# had_ret.net
KiCad netlist of a schematic drawn in EAGLE
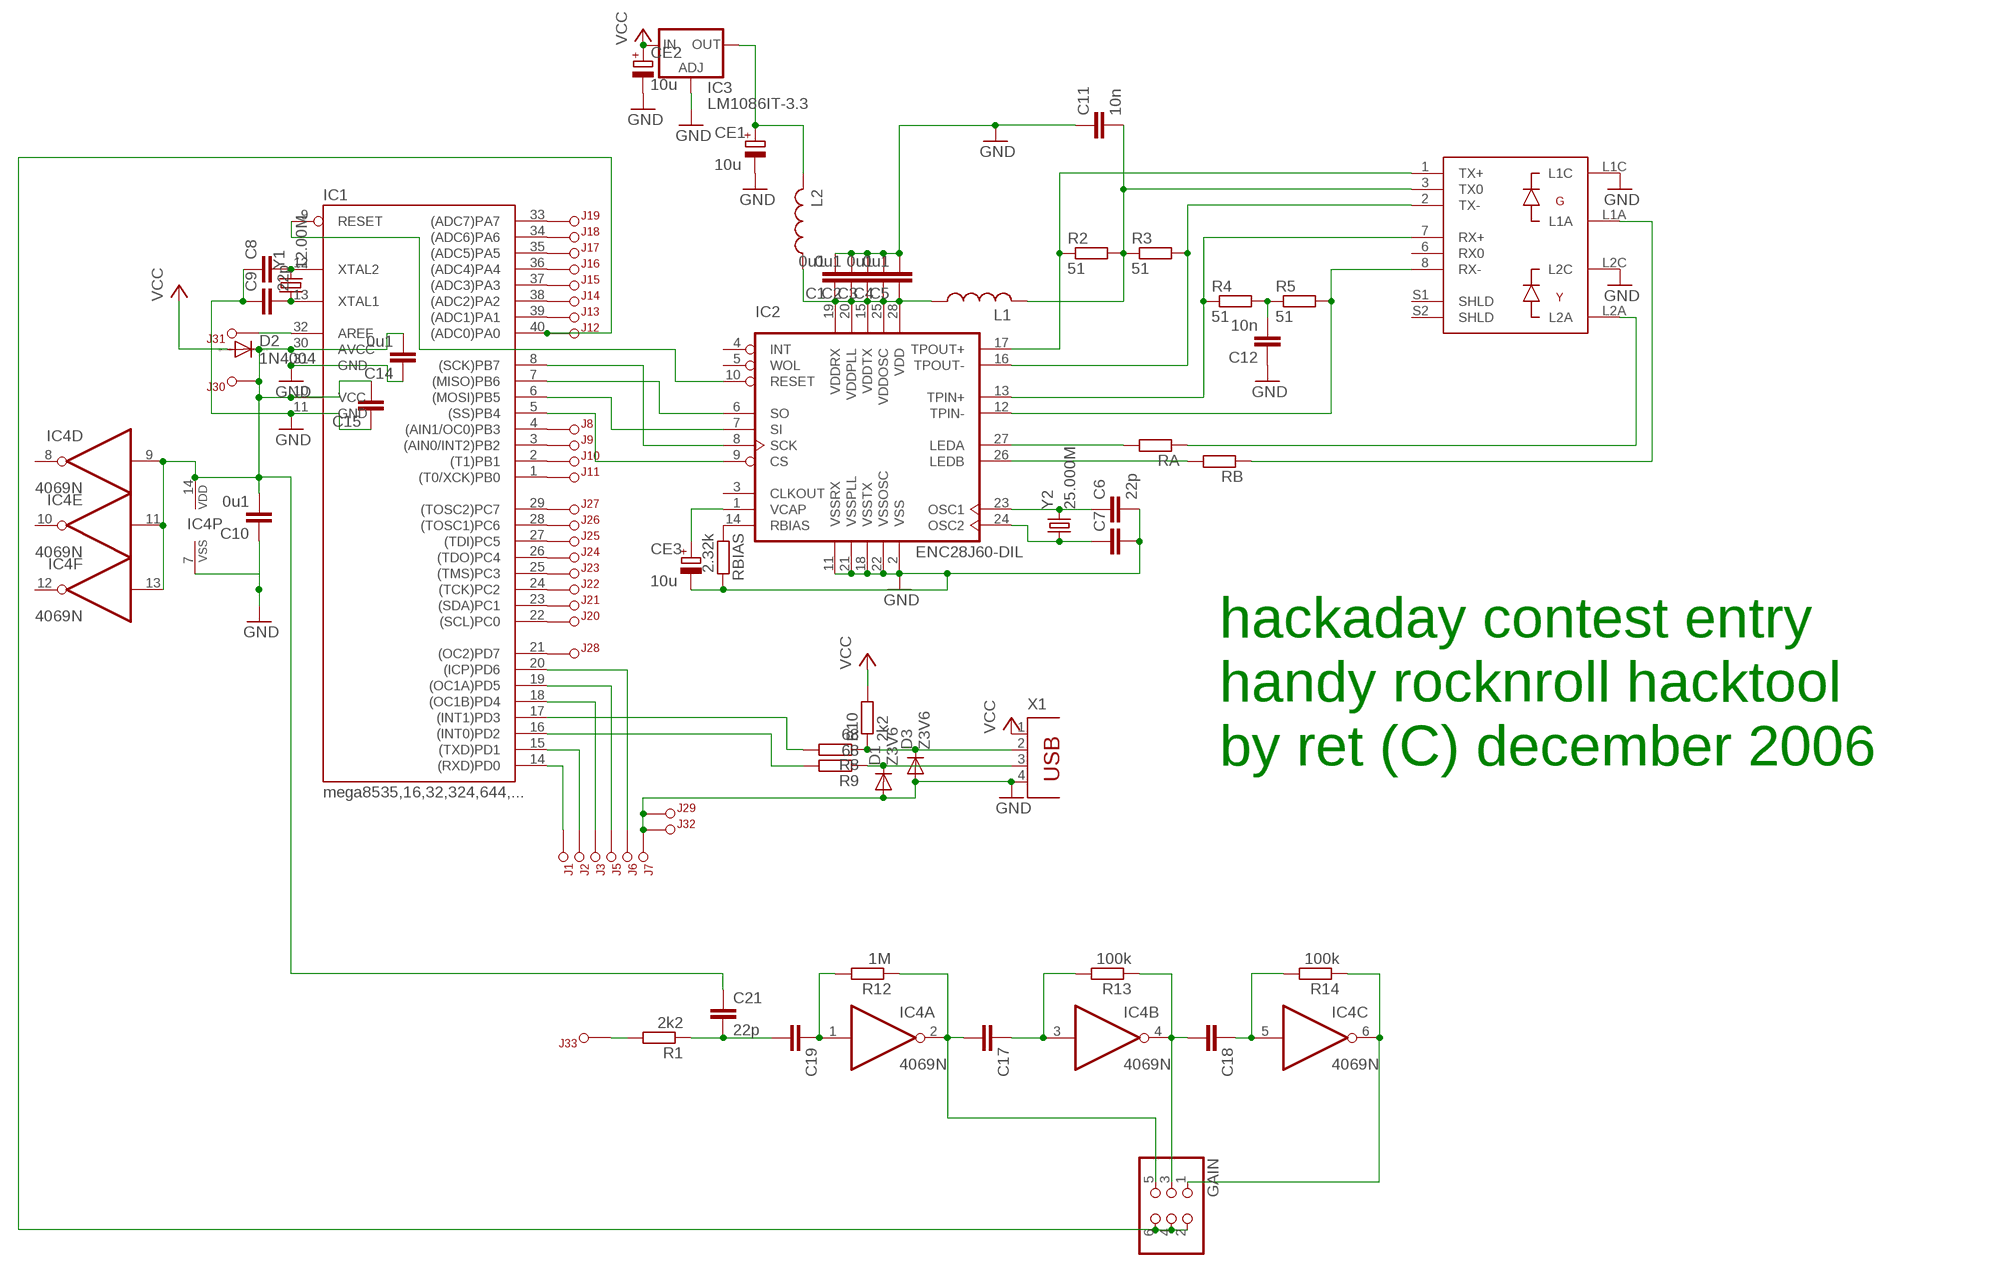
[diagram p0: schematic, sheet 1]

(export (version "E")
  (design (tool "Eeschema 10.0.6"))
  (components
    (comp (ref "C1")
      (value "0u1")
      (footprint "eagle-import:0805")
      (libsource (lib "eagle-import") (part "C0805"))
    )
    (comp (ref "C2")
      (value "0u1")
      (footprint "eagle-import:0805")
      (libsource (lib "eagle-import") (part "C0805"))
    )
    (comp (ref "C3")
      (value "C0805")
      (footprint "eagle-import:0805")
      (libsource (lib "eagle-import") (part "C0805"))
    )
    (comp (ref "C4")
      (value "0u1")
      (footprint "eagle-import:0805")
      (libsource (lib "eagle-import") (part "C0805"))
    )
    (comp (ref "C5")
      (value "0u1")
      (footprint "eagle-import:0805")
      (libsource (lib "eagle-import") (part "C0805"))
    )
    (comp (ref "C6")
      (value "22p")
      (footprint "eagle-import:0805")
      (libsource (lib "eagle-import") (part "C0805"))
    )
    (comp (ref "C7")
      (value "C0805")
      (footprint "eagle-import:0805")
      (libsource (lib "eagle-import") (part "C0805"))
    )
    (comp (ref "C8")
      (value "C0805")
      (footprint "eagle-import:0805")
      (libsource (lib "eagle-import") (part "C0805"))
    )
    (comp (ref "C9")
      (value "22p")
      (footprint "eagle-import:0805")
      (libsource (lib "eagle-import") (part "C0805"))
    )
    (comp (ref "C10")
      (value "0u1")
      (footprint "eagle-import:0805")
      (libsource (lib "eagle-import") (part "C0805"))
    )
    (comp (ref "C11")
      (value "10n")
      (footprint "eagle-import:0805")
      (libsource (lib "eagle-import") (part "C0805"))
    )
    (comp (ref "C12")
      (value "10n")
      (footprint "eagle-import:0805")
      (libsource (lib "eagle-import") (part "C0805"))
    )
    (comp (ref "C14")
      (value "0u1")
      (footprint "eagle-import:0805")
      (libsource (lib "eagle-import") (part "C0805"))
    )
    (comp (ref "C15")
      (value "C0805")
      (footprint "eagle-import:0805")
      (libsource (lib "eagle-import") (part "C0805"))
    )
    (comp (ref "C17")
      (value "C0805")
      (footprint "eagle-import:0805")
      (libsource (lib "eagle-import") (part "C0805"))
    )
    (comp (ref "C18")
      (value "C0805")
      (footprint "eagle-import:0805")
      (libsource (lib "eagle-import") (part "C0805"))
    )
    (comp (ref "C19")
      (value "C0805")
      (footprint "eagle-import:0805")
      (libsource (lib "eagle-import") (part "C0805"))
    )
    (comp (ref "C21")
      (value "22p")
      (footprint "eagle-import:0805")
      (libsource (lib "eagle-import") (part "C0805"))
    )
    (comp (ref "CE1")
      (value "10u")
      (footprint "eagle-import:CT3528")
      (libsource (lib "eagle-import") (part "CPOL-EUCT3528"))
    )
    (comp (ref "CE2")
      (value "10u")
      (footprint "eagle-import:CT3528")
      (libsource (lib "eagle-import") (part "CPOL-EUCT3528"))
    )
    (comp (ref "CE3")
      (value "10u")
      (footprint "eagle-import:CT3528")
      (libsource (lib "eagle-import") (part "CPOL-EUCT3528"))
    )
    (comp (ref "D1")
      (value "Z3V6")
      (footprint "eagle-import:DIODE")
      (libsource (lib "eagle-import") (part "DIODE"))
    )
    (comp (ref "D2")
      (value "1N4004")
      (footprint "eagle-import:DO41-10")
      (libsource (lib "eagle-import") (part "1N4004"))
    )
    (comp (ref "D3")
      (value "Z3V6")
      (footprint "eagle-import:DIODE")
      (libsource (lib "eagle-import") (part "DIODE"))
    )
    (comp (ref "GAIN")
      (value "PINHD-2X3")
      (footprint "eagle-import:2X03")
      (libsource (lib "eagle-import") (part "PINHD-2X3"))
    )
    (comp (ref "IC1")
      (value "mega8535,16,32,324,644,...")
      (footprint "eagle-import:DIL40")
      (fields (field (name "MPN") "ATMEGA16-16PU"))
      (libsource (lib "eagle-import") (part "MEGA16-P"))
    )
    (comp (ref "IC2")
      (value "ENC28J60-DIL")
      (footprint "eagle-import:DIL28-3")
      (libsource (lib "eagle-import") (part "ENC28J60-DIL"))
    )
    (comp (ref "IC3")
      (value "LM1086IT-3.3")
      (footprint "eagle-import:317TS")
      (libsource (lib "eagle-import") (part "LM317TS"))
    )
    (comp (ref "IC4")
      (value "4069N")
      (footprint "eagle-import:DIL14")
      (libsource (lib "eagle-import") (part "4069N"))
    )
    (comp (ref "J1")
      (value "PINMA01")
      (footprint "eagle-import:MA01-1PIN")
      (libsource (lib "eagle-import") (part "PINMA01"))
    )
    (comp (ref "J2")
      (value "PINMA01")
      (footprint "eagle-import:MA01-1PIN")
      (libsource (lib "eagle-import") (part "PINMA01"))
    )
    (comp (ref "J3")
      (value "PINMA01")
      (footprint "eagle-import:MA01-1PIN")
      (libsource (lib "eagle-import") (part "PINMA01"))
    )
    (comp (ref "J4")
      (value "8P8C-TRAF")
      (footprint "eagle-import:8P8C-TRAF")
      (libsource (lib "eagle-import") (part "8P8C-TRAF"))
    )
    (comp (ref "J5")
      (value "PINMA01")
      (footprint "eagle-import:MA01-1PIN")
      (libsource (lib "eagle-import") (part "PINMA01"))
    )
    (comp (ref "J6")
      (value "PINMA01")
      (footprint "eagle-import:MA01-1PIN")
      (libsource (lib "eagle-import") (part "PINMA01"))
    )
    (comp (ref "J7")
      (value "PINMA01")
      (footprint "eagle-import:MA01-1PIN")
      (libsource (lib "eagle-import") (part "PINMA01"))
    )
    (comp (ref "J8")
      (value "PINMA01")
      (footprint "eagle-import:MA01-1PIN")
      (libsource (lib "eagle-import") (part "PINMA01"))
    )
    (comp (ref "J9")
      (value "PINMA01")
      (footprint "eagle-import:MA01-1PIN")
      (libsource (lib "eagle-import") (part "PINMA01"))
    )
    (comp (ref "J10")
      (value "PINMA01")
      (footprint "eagle-import:MA01-1PIN")
      (libsource (lib "eagle-import") (part "PINMA01"))
    )
    (comp (ref "J11")
      (value "PINMA01")
      (footprint "eagle-import:MA01-1PIN")
      (libsource (lib "eagle-import") (part "PINMA01"))
    )
    (comp (ref "J12")
      (value "PINMA01")
      (footprint "eagle-import:MA01-1PIN")
      (libsource (lib "eagle-import") (part "PINMA01"))
    )
    (comp (ref "J13")
      (value "PINMA01")
      (footprint "eagle-import:MA01-1PIN")
      (libsource (lib "eagle-import") (part "PINMA01"))
    )
    (comp (ref "J14")
      (value "PINMA01")
      (footprint "eagle-import:MA01-1PIN")
      (libsource (lib "eagle-import") (part "PINMA01"))
    )
    (comp (ref "J15")
      (value "PINMA01")
      (footprint "eagle-import:MA01-1PIN")
      (libsource (lib "eagle-import") (part "PINMA01"))
    )
    (comp (ref "J16")
      (value "PINMA01")
      (footprint "eagle-import:MA01-1PIN")
      (libsource (lib "eagle-import") (part "PINMA01"))
    )
    (comp (ref "J17")
      (value "PINMA01")
      (footprint "eagle-import:MA01-1PIN")
      (libsource (lib "eagle-import") (part "PINMA01"))
    )
    (comp (ref "J18")
      (value "PINMA01")
      (footprint "eagle-import:MA01-1PIN")
      (libsource (lib "eagle-import") (part "PINMA01"))
    )
    (comp (ref "J19")
      (value "PINMA01")
      (footprint "eagle-import:MA01-1PIN")
      (libsource (lib "eagle-import") (part "PINMA01"))
    )
    (comp (ref "J20")
      (value "PINMA01")
      (footprint "eagle-import:MA01-1PIN")
      (libsource (lib "eagle-import") (part "PINMA01"))
    )
    (comp (ref "J21")
      (value "PINMA01")
      (footprint "eagle-import:MA01-1PIN")
      (libsource (lib "eagle-import") (part "PINMA01"))
    )
    (comp (ref "J22")
      (value "PINMA01")
      (footprint "eagle-import:MA01-1PIN")
      (libsource (lib "eagle-import") (part "PINMA01"))
    )
    (comp (ref "J23")
      (value "PINMA01")
      (footprint "eagle-import:MA01-1PIN")
      (libsource (lib "eagle-import") (part "PINMA01"))
    )
    (comp (ref "J24")
      (value "PINMA01")
      (footprint "eagle-import:MA01-1PIN")
      (libsource (lib "eagle-import") (part "PINMA01"))
    )
    (comp (ref "J25")
      (value "PINMA01")
      (footprint "eagle-import:MA01-1PIN")
      (libsource (lib "eagle-import") (part "PINMA01"))
    )
    (comp (ref "J26")
      (value "PINMA01")
      (footprint "eagle-import:MA01-1PIN")
      (libsource (lib "eagle-import") (part "PINMA01"))
    )
    (comp (ref "J27")
      (value "PINMA01")
      (footprint "eagle-import:MA01-1PIN")
      (libsource (lib "eagle-import") (part "PINMA01"))
    )
    (comp (ref "J28")
      (value "PINMA01")
      (footprint "eagle-import:MA01-1PIN")
      (libsource (lib "eagle-import") (part "PINMA01"))
    )
    (comp (ref "J29")
      (value "PINMA01")
      (footprint "eagle-import:MA01-1PIN")
      (libsource (lib "eagle-import") (part "PINMA01"))
    )
    (comp (ref "J30")
      (value "PINMA01")
      (footprint "eagle-import:MA01-1PIN")
      (libsource (lib "eagle-import") (part "PINMA01"))
    )
    (comp (ref "J31")
      (value "PINMA01")
      (footprint "eagle-import:MA01-1PIN")
      (libsource (lib "eagle-import") (part "PINMA01"))
    )
    (comp (ref "J32")
      (value "PINMA01")
      (footprint "eagle-import:MA01-1PIN")
      (libsource (lib "eagle-import") (part "PINMA01"))
    )
    (comp (ref "J33")
      (value "PINMA01")
      (footprint "eagle-import:MA01-1PIN")
      (libsource (lib "eagle-import") (part "PINMA01"))
    )
    (comp (ref "L1")
      (value "L0805")
      (footprint "eagle-import:0805")
      (libsource (lib "eagle-import") (part "L0805"))
    )
    (comp (ref "L2")
      (value "L0805")
      (footprint "eagle-import:0805")
      (libsource (lib "eagle-import") (part "L0805"))
    )
    (comp (ref "R1")
      (value "2k2")
      (footprint "eagle-import:0805")
      (libsource (lib "eagle-import") (part "R0805"))
    )
    (comp (ref "R2")
      (value "51")
      (footprint "eagle-import:0805")
      (libsource (lib "eagle-import") (part "R0805"))
    )
    (comp (ref "R3")
      (value "51")
      (footprint "eagle-import:0805")
      (libsource (lib "eagle-import") (part "R0805"))
    )
    (comp (ref "R4")
      (value "51")
      (footprint "eagle-import:0805")
      (libsource (lib "eagle-import") (part "R0805"))
    )
    (comp (ref "R5")
      (value "51")
      (footprint "eagle-import:0805")
      (libsource (lib "eagle-import") (part "R0805"))
    )
    (comp (ref "R8")
      (value "68")
      (footprint "eagle-import:0805")
      (libsource (lib "eagle-import") (part "R0805"))
    )
    (comp (ref "R9")
      (value "68")
      (footprint "eagle-import:0805")
      (libsource (lib "eagle-import") (part "R0805"))
    )
    (comp (ref "R10")
      (value "2k2")
      (footprint "eagle-import:0805")
      (libsource (lib "eagle-import") (part "R0805"))
    )
    (comp (ref "R12")
      (value "1M")
      (footprint "eagle-import:0805")
      (libsource (lib "eagle-import") (part "R0805"))
    )
    (comp (ref "R13")
      (value "100k")
      (footprint "eagle-import:0805")
      (libsource (lib "eagle-import") (part "R0805"))
    )
    (comp (ref "R14")
      (value "100k")
      (footprint "eagle-import:0805")
      (libsource (lib "eagle-import") (part "R0805"))
    )
    (comp (ref "RA")
      (value "R-EU_0204/5")
      (footprint "eagle-import:0204_5")
      (libsource (lib "eagle-import") (part "R-EU_0204/5"))
    )
    (comp (ref "RB")
      (value "R-EU_0204/5")
      (footprint "eagle-import:0204_5")
      (libsource (lib "eagle-import") (part "R-EU_0204/5"))
    )
    (comp (ref "RBIAS")
      (value "2.32k")
      (footprint "eagle-import:0204_7")
      (libsource (lib "eagle-import") (part "R-EU_0204/7"))
    )
    (comp (ref "X1")
      (value "PN61729")
      (footprint "eagle-import:PN61729")
      (libsource (lib "eagle-import") (part "PN61729"))
    )
    (comp (ref "Y1")
      (value "12.00M")
      (footprint "eagle-import:HC49_S")
      (libsource (lib "eagle-import") (part "CRYSTALHC49S"))
    )
    (comp (ref "Y2")
      (value "25.000M")
      (footprint "eagle-import:HC49_S")
      (libsource (lib "eagle-import") (part "CRYSTALHC49S"))
    )
  )
  (nets
    (net (code "1") (name "GND") (class "Default")
      (node (ref "C1") (pin "2") (pinfunction "2_2") (pintype "passive"))
      (node (ref "C10") (pin "1") (pinfunction "1_1") (pintype "passive"))
      (node (ref "C11") (pin "1") (pinfunction "1_1") (pintype "passive"))
      (node (ref "C12") (pin "1") (pinfunction "1_1") (pintype "passive"))
      (node (ref "C14") (pin "1") (pinfunction "1_1") (pintype "passive"))
      (node (ref "C15") (pin "1") (pinfunction "1_1") (pintype "passive"))
      (node (ref "C2") (pin "2") (pinfunction "2_2") (pintype "passive"))
      (node (ref "C3") (pin "2") (pinfunction "2_2") (pintype "passive"))
      (node (ref "C4") (pin "2") (pinfunction "2_2") (pintype "passive"))
      (node (ref "C5") (pin "2") (pinfunction "2_2") (pintype "passive"))
      (node (ref "C6") (pin "2") (pinfunction "2_2") (pintype "passive"))
      (node (ref "C7") (pin "2") (pinfunction "2_2") (pintype "passive"))
      (node (ref "C8") (pin "1") (pinfunction "1_1") (pintype "passive"))
      (node (ref "C9") (pin "1") (pinfunction "1_1") (pintype "passive"))
      (node (ref "CE1") (pin "-") (pinfunction "-_-") (pintype "passive"))
      (node (ref "CE2") (pin "-") (pinfunction "-_-") (pintype "passive"))
      (node (ref "CE3") (pin "-") (pinfunction "-_-") (pintype "passive"))
      (node (ref "D1") (pin "A") (pinfunction "A_A") (pintype "passive"))
      (node (ref "D3") (pin "A") (pinfunction "A_A") (pintype "passive"))
      (node (ref "IC1") (pin "11") (pinfunction "GND_11") (pintype "power_in"))
      (node (ref "IC1") (pin "31") (pinfunction "GND_31") (pintype "power_in"))
      (node (ref "IC2") (pin "11") (pinfunction "VSSRX_11") (pintype "power_in"))
      (node (ref "IC2") (pin "18") (pinfunction "VSSTX_18") (pintype "power_in"))
      (node (ref "IC2") (pin "2") (pinfunction "VSS_2") (pintype "power_in"))
      (node (ref "IC2") (pin "21") (pinfunction "VSSPLL_21") (pintype "power_in"))
      (node (ref "IC2") (pin "22") (pinfunction "VSSOSC_22") (pintype "power_in"))
      (node (ref "IC3") (pin "1") (pinfunction "ADJ_1") (pintype "input"))
      (node (ref "IC4") (pin "7") (pinfunction "VSS_7") (pintype "power_in"))
      (node (ref "J29") (pin "1") (pinfunction "P$1_1") (pintype "bidirectional"))
      (node (ref "J32") (pin "1") (pinfunction "P$1_1") (pintype "bidirectional"))
      (node (ref "J4") (pin "L1C") (pinfunction "L1C_L1C") (pintype "bidirectional"))
      (node (ref "J4") (pin "L2C") (pinfunction "L2C_L2C") (pintype "bidirectional"))
      (node (ref "J7") (pin "1") (pinfunction "P$1_1") (pintype "bidirectional"))
      (node (ref "RBIAS") (pin "2") (pinfunction "2_2") (pintype "passive"))
      (node (ref "X1") (pin "4") (pinfunction "4_4") (pintype "passive"))
    )
    (net (code "2") (name "Net-(C12-Pad2)") (class "Default")
      (node (ref "C12") (pin "2") (pinfunction "2_2") (pintype "passive"))
      (node (ref "R4") (pin "2") (pinfunction "2_2") (pintype "passive"))
      (node (ref "R5") (pin "1") (pinfunction "1_1") (pintype "passive"))
    )
    (net (code "3") (name "Net-(C19-Pad2)") (class "Default")
      (node (ref "C19") (pin "2") (pinfunction "2_2") (pintype "passive"))
      (node (ref "C21") (pin "2") (pinfunction "2_2") (pintype "passive"))
      (node (ref "R1") (pin "1") (pinfunction "1_1") (pintype "passive"))
    )
    (net (code "4") (name "Net-(D1-C)") (class "Default")
      (node (ref "D1") (pin "K") (pinfunction "C_K") (pintype "passive"))
      (node (ref "R9") (pin "1") (pinfunction "1_1") (pintype "passive"))
      (node (ref "X1") (pin "3") (pinfunction "3_3") (pintype "passive"))
    )
    (net (code "5") (name "Net-(D3-C)") (class "Default")
      (node (ref "D3") (pin "K") (pinfunction "C_K") (pintype "passive"))
      (node (ref "R10") (pin "1") (pinfunction "1_1") (pintype "passive"))
      (node (ref "R8") (pin "1") (pinfunction "1_1") (pintype "passive"))
      (node (ref "X1") (pin "2") (pinfunction "2_2") (pintype "passive"))
    )
    (net (code "6") (name "Net-(IC1-(ADC0)PA0)") (class "Default")
      (node (ref "GAIN") (pin "2") (pinfunction "2_2") (pintype "passive"))
      (node (ref "GAIN") (pin "4") (pinfunction "4_4") (pintype "passive"))
      (node (ref "GAIN") (pin "6") (pinfunction "6_6") (pintype "passive"))
      (node (ref "IC1") (pin "40") (pinfunction "(ADC0)PA0_40") (pintype "bidirectional"))
      (node (ref "J12") (pin "1") (pinfunction "P$1_1") (pintype "bidirectional"))
    )
    (net (code "7") (name "Net-(IC1-(ADC1)PA1)") (class "Default")
      (node (ref "IC1") (pin "39") (pinfunction "(ADC1)PA1_39") (pintype "bidirectional"))
      (node (ref "J13") (pin "1") (pinfunction "P$1_1") (pintype "bidirectional"))
    )
    (net (code "8") (name "Net-(IC1-(ADC2)PA2)") (class "Default")
      (node (ref "IC1") (pin "38") (pinfunction "(ADC2)PA2_38") (pintype "bidirectional"))
      (node (ref "J14") (pin "1") (pinfunction "P$1_1") (pintype "bidirectional"))
    )
    (net (code "9") (name "Net-(IC1-(ADC3)PA3)") (class "Default")
      (node (ref "IC1") (pin "37") (pinfunction "(ADC3)PA3_37") (pintype "bidirectional"))
      (node (ref "J15") (pin "1") (pinfunction "P$1_1") (pintype "bidirectional"))
    )
    (net (code "10") (name "Net-(IC1-(ADC4)PA4)") (class "Default")
      (node (ref "IC1") (pin "36") (pinfunction "(ADC4)PA4_36") (pintype "bidirectional"))
      (node (ref "J16") (pin "1") (pinfunction "P$1_1") (pintype "bidirectional"))
    )
    (net (code "11") (name "Net-(IC1-(ADC5)PA5)") (class "Default")
      (node (ref "IC1") (pin "35") (pinfunction "(ADC5)PA5_35") (pintype "bidirectional"))
      (node (ref "J17") (pin "1") (pinfunction "P$1_1") (pintype "bidirectional"))
    )
    (net (code "12") (name "Net-(IC1-(ADC6)PA6)") (class "Default")
      (node (ref "IC1") (pin "34") (pinfunction "(ADC6)PA6_34") (pintype "bidirectional"))
      (node (ref "J18") (pin "1") (pinfunction "P$1_1") (pintype "bidirectional"))
    )
    (net (code "13") (name "Net-(IC1-(ADC7)PA7)") (class "Default")
      (node (ref "IC1") (pin "33") (pinfunction "(ADC7)PA7_33") (pintype "bidirectional"))
      (node (ref "J19") (pin "1") (pinfunction "P$1_1") (pintype "bidirectional"))
    )
    (net (code "14") (name "Net-(IC1-(AIN0{slash}INT2)PB2)") (class "Default")
      (node (ref "IC1") (pin "3") (pinfunction "(AIN0/INT2)PB2_3") (pintype "bidirectional"))
      (node (ref "J9") (pin "1") (pinfunction "P$1_1") (pintype "bidirectional"))
    )
    (net (code "15") (name "Net-(IC1-(AIN1{slash}OC0)PB3)") (class "Default")
      (node (ref "IC1") (pin "4") (pinfunction "(AIN1/OC0)PB3_4") (pintype "bidirectional"))
      (node (ref "J8") (pin "1") (pinfunction "P$1_1") (pintype "bidirectional"))
    )
    (net (code "16") (name "Net-(IC1-(ICP)PD6)") (class "Default")
      (node (ref "IC1") (pin "20") (pinfunction "(ICP)PD6_20") (pintype "bidirectional"))
      (node (ref "J6") (pin "1") (pinfunction "P$1_1") (pintype "bidirectional"))
    )
    (net (code "17") (name "Net-(IC1-(INT0)PD2)") (class "Default")
      (node (ref "IC1") (pin "16") (pinfunction "(INT0)PD2_16") (pintype "bidirectional"))
      (node (ref "R9") (pin "2") (pinfunction "2_2") (pintype "passive"))
    )
    (net (code "18") (name "Net-(IC1-(INT1)PD3)") (class "Default")
      (node (ref "IC1") (pin "17") (pinfunction "(INT1)PD3_17") (pintype "bidirectional"))
      (node (ref "R8") (pin "2") (pinfunction "2_2") (pintype "passive"))
    )
    (net (code "19") (name "Net-(IC1-(MISO)PB6)") (class "Default")
      (node (ref "IC1") (pin "7") (pinfunction "(MISO)PB6_7") (pintype "bidirectional"))
      (node (ref "IC2") (pin "6") (pinfunction "SO_6") (pintype "output"))
    )
    (net (code "20") (name "Net-(IC1-(MOSI)PB5)") (class "Default")
      (node (ref "IC1") (pin "6") (pinfunction "(MOSI)PB5_6") (pintype "bidirectional"))
      (node (ref "IC2") (pin "7") (pinfunction "SI_7") (pintype "input"))
    )
    (net (code "21") (name "Net-(IC1-(OC1A)PD5)") (class "Default")
      (node (ref "IC1") (pin "19") (pinfunction "(OC1A)PD5_19") (pintype "bidirectional"))
      (node (ref "J5") (pin "1") (pinfunction "P$1_1") (pintype "bidirectional"))
    )
    (net (code "22") (name "Net-(IC1-(OC1B)PD4)") (class "Default")
      (node (ref "IC1") (pin "18") (pinfunction "(OC1B)PD4_18") (pintype "bidirectional"))
      (node (ref "J3") (pin "1") (pinfunction "P$1_1") (pintype "bidirectional"))
    )
    (net (code "23") (name "Net-(IC1-(OC2)PD7)") (class "Default")
      (node (ref "IC1") (pin "21") (pinfunction "(OC2)PD7_21") (pintype "bidirectional"))
      (node (ref "J28") (pin "1") (pinfunction "P$1_1") (pintype "bidirectional"))
    )
    (net (code "24") (name "Net-(IC1-(RXD)PD0)") (class "Default")
      (node (ref "IC1") (pin "14") (pinfunction "(RXD)PD0_14") (pintype "bidirectional"))
      (node (ref "J1") (pin "1") (pinfunction "P$1_1") (pintype "bidirectional"))
    )
    (net (code "25") (name "Net-(IC1-(SCK)PB7)") (class "Default")
      (node (ref "IC1") (pin "8") (pinfunction "(SCK)PB7_8") (pintype "bidirectional"))
      (node (ref "IC2") (pin "8") (pinfunction "SCK_8") (pintype "input"))
    )
    (net (code "26") (name "Net-(IC1-(SCL)PC0)") (class "Default")
      (node (ref "IC1") (pin "22") (pinfunction "(SCL)PC0_22") (pintype "bidirectional"))
      (node (ref "J20") (pin "1") (pinfunction "P$1_1") (pintype "bidirectional"))
    )
    (net (code "27") (name "Net-(IC1-(SDA)PC1)") (class "Default")
      (node (ref "IC1") (pin "23") (pinfunction "(SDA)PC1_23") (pintype "bidirectional"))
      (node (ref "J21") (pin "1") (pinfunction "P$1_1") (pintype "bidirectional"))
    )
    (net (code "28") (name "Net-(IC1-(SS)PB4)") (class "Default")
      (node (ref "IC1") (pin "5") (pinfunction "(SS)PB4_5") (pintype "bidirectional"))
      (node (ref "IC2") (pin "9") (pinfunction "CS_9") (pintype "input"))
    )
    (net (code "29") (name "Net-(IC1-(T0{slash}XCK)PB0)") (class "Default")
      (node (ref "IC1") (pin "1") (pinfunction "(T0/XCK)PB0_1") (pintype "bidirectional"))
      (node (ref "J11") (pin "1") (pinfunction "P$1_1") (pintype "bidirectional"))
    )
    (net (code "30") (name "Net-(IC1-(T1)PB1)") (class "Default")
      (node (ref "IC1") (pin "2") (pinfunction "(T1)PB1_2") (pintype "bidirectional"))
      (node (ref "J10") (pin "1") (pinfunction "P$1_1") (pintype "bidirectional"))
    )
    (net (code "31") (name "Net-(IC1-(TCK)PC2)") (class "Default")
      (node (ref "IC1") (pin "24") (pinfunction "(TCK)PC2_24") (pintype "bidirectional"))
      (node (ref "J22") (pin "1") (pinfunction "P$1_1") (pintype "bidirectional"))
    )
    (net (code "32") (name "Net-(IC1-(TDI)PC5)") (class "Default")
      (node (ref "IC1") (pin "27") (pinfunction "(TDI)PC5_27") (pintype "bidirectional"))
      (node (ref "J25") (pin "1") (pinfunction "P$1_1") (pintype "bidirectional"))
    )
    (net (code "33") (name "Net-(IC1-(TDO)PC4)") (class "Default")
      (node (ref "IC1") (pin "26") (pinfunction "(TDO)PC4_26") (pintype "bidirectional"))
      (node (ref "J24") (pin "1") (pinfunction "P$1_1") (pintype "bidirectional"))
    )
    (net (code "34") (name "Net-(IC1-(TMS)PC3)") (class "Default")
      (node (ref "IC1") (pin "25") (pinfunction "(TMS)PC3_25") (pintype "bidirectional"))
      (node (ref "J23") (pin "1") (pinfunction "P$1_1") (pintype "bidirectional"))
    )
    (net (code "35") (name "Net-(IC1-(TOSC1)PC6)") (class "Default")
      (node (ref "IC1") (pin "28") (pinfunction "(TOSC1)PC6_28") (pintype "bidirectional"))
      (node (ref "J26") (pin "1") (pinfunction "P$1_1") (pintype "bidirectional"))
    )
    (net (code "36") (name "Net-(IC1-(TOSC2)PC7)") (class "Default")
      (node (ref "IC1") (pin "29") (pinfunction "(TOSC2)PC7_29") (pintype "bidirectional"))
      (node (ref "J27") (pin "1") (pinfunction "P$1_1") (pintype "bidirectional"))
    )
    (net (code "37") (name "Net-(IC1-(TXD)PD1)") (class "Default")
      (node (ref "IC1") (pin "15") (pinfunction "(TXD)PD1_15") (pintype "bidirectional"))
      (node (ref "J2") (pin "1") (pinfunction "P$1_1") (pintype "bidirectional"))
    )
    (net (code "38") (name "Net-(IC1-AREF)") (class "Default")
      (node (ref "IC1") (pin "32") (pinfunction "AREF_32") (pintype "passive"))
      (node (ref "J31") (pin "1") (pinfunction "P$1_1") (pintype "bidirectional"))
    )
    (net (code "39") (name "Net-(IC1-AVCC)") (class "Default")
      (node (ref "C10") (pin "2") (pinfunction "2_2") (pintype "passive"))
      (node (ref "C14") (pin "2") (pinfunction "2_2") (pintype "passive"))
      (node (ref "C15") (pin "2") (pinfunction "2_2") (pintype "passive"))
      (node (ref "C21") (pin "1") (pinfunction "1_1") (pintype "passive"))
      (node (ref "D2") (pin "C") (pinfunction "C_C") (pintype "passive"))
      (node (ref "IC1") (pin "10") (pinfunction "VCC_10") (pintype "power_in"))
      (node (ref "IC1") (pin "30") (pinfunction "AVCC_30") (pintype "power_in"))
      (node (ref "IC4") (pin "11") (pinfunction "I_11") (pintype "input"))
      (node (ref "IC4") (pin "13") (pinfunction "I_13") (pintype "input"))
      (node (ref "IC4") (pin "14") (pinfunction "VDD_14") (pintype "power_in"))
      (node (ref "IC4") (pin "9") (pinfunction "I_9") (pintype "input"))
      (node (ref "J30") (pin "1") (pinfunction "P$1_1") (pintype "bidirectional"))
    )
    (net (code "40") (name "Net-(IC1-RESET)") (class "Default")
      (node (ref "IC1") (pin "9") (pinfunction "RESET_9") (pintype "input"))
      (node (ref "IC2") (pin "10") (pinfunction "RESET_10") (pintype "input"))
    )
    (net (code "41") (name "Net-(IC1-XTAL1)") (class "Default")
      (node (ref "C9") (pin "2") (pinfunction "2_2") (pintype "passive"))
      (node (ref "IC1") (pin "13") (pinfunction "XTAL1_13") (pintype "bidirectional"))
      (node (ref "Y1") (pin "1") (pinfunction "1_1") (pintype "passive"))
    )
    (net (code "42") (name "Net-(IC1-XTAL2)") (class "Default")
      (node (ref "C8") (pin "2") (pinfunction "2_2") (pintype "passive"))
      (node (ref "IC1") (pin "12") (pinfunction "XTAL2_12") (pintype "bidirectional"))
      (node (ref "Y1") (pin "2") (pinfunction "2_2") (pintype "passive"))
    )
    (net (code "43") (name "Net-(IC2-LEDA)") (class "Default")
      (node (ref "IC2") (pin "27") (pinfunction "LEDA_27") (pintype "output"))
      (node (ref "RA") (pin "2") (pinfunction "2_2") (pintype "passive"))
    )
    (net (code "44") (name "Net-(IC2-LEDB)") (class "Default")
      (node (ref "IC2") (pin "26") (pinfunction "LEDB_26") (pintype "output"))
      (node (ref "RB") (pin "2") (pinfunction "2_2") (pintype "passive"))
    )
    (net (code "45") (name "Net-(IC2-OSC1)") (class "Default")
      (node (ref "C6") (pin "1") (pinfunction "1_1") (pintype "passive"))
      (node (ref "IC2") (pin "23") (pinfunction "OSC1_23") (pintype "input"))
      (node (ref "Y2") (pin "2") (pinfunction "2_2") (pintype "passive"))
    )
    (net (code "46") (name "Net-(IC2-OSC2)") (class "Default")
      (node (ref "C7") (pin "1") (pinfunction "1_1") (pintype "passive"))
      (node (ref "IC2") (pin "24") (pinfunction "OSC2_24") (pintype "output"))
      (node (ref "Y2") (pin "1") (pinfunction "1_1") (pintype "passive"))
    )
    (net (code "47") (name "Net-(IC2-RBIAS)") (class "Default")
      (node (ref "IC2") (pin "14") (pinfunction "RBIAS_14") (pintype "passive"))
      (node (ref "RBIAS") (pin "1") (pinfunction "1_1") (pintype "passive"))
    )
    (net (code "48") (name "Net-(IC2-TPIN+)") (class "Default")
      (node (ref "IC2") (pin "13") (pinfunction "TPIN+_13") (pintype "input"))
      (node (ref "J4") (pin "7") (pinfunction "RX+_7") (pintype "bidirectional"))
      (node (ref "R4") (pin "1") (pinfunction "1_1") (pintype "passive"))
    )
    (net (code "49") (name "Net-(IC2-TPIN-)") (class "Default")
      (node (ref "IC2") (pin "12") (pinfunction "TPIN-_12") (pintype "input"))
      (node (ref "J4") (pin "8") (pinfunction "RX-_8") (pintype "bidirectional"))
      (node (ref "R5") (pin "2") (pinfunction "2_2") (pintype "passive"))
    )
    (net (code "50") (name "Net-(IC2-TPOUT+)") (class "Default")
      (node (ref "IC2") (pin "17") (pinfunction "TPOUT+_17") (pintype "output"))
      (node (ref "J4") (pin "1") (pinfunction "TX+_1") (pintype "bidirectional"))
      (node (ref "R2") (pin "1") (pinfunction "1_1") (pintype "passive"))
    )
    (net (code "51") (name "Net-(IC2-TPOUT-)") (class "Default")
      (node (ref "IC2") (pin "16") (pinfunction "TPOUT-_16") (pintype "output"))
      (node (ref "J4") (pin "2") (pinfunction "TX-_2") (pintype "bidirectional"))
      (node (ref "R3") (pin "2") (pinfunction "2_2") (pintype "passive"))
    )
    (net (code "52") (name "Net-(IC2-VCAP)") (class "Default")
      (node (ref "CE3") (pin "+") (pinfunction "+_+") (pintype "passive"))
      (node (ref "IC2") (pin "1") (pinfunction "VCAP_1") (pintype "power_in"))
    )
    (net (code "53") (name "Net-(IC2-VDD)") (class "Default")
      (node (ref "C1") (pin "1") (pinfunction "1_1") (pintype "passive"))
      (node (ref "C2") (pin "1") (pinfunction "1_1") (pintype "passive"))
      (node (ref "C3") (pin "1") (pinfunction "1_1") (pintype "passive"))
      (node (ref "C4") (pin "1") (pinfunction "1_1") (pintype "passive"))
      (node (ref "C5") (pin "1") (pinfunction "1_1") (pintype "passive"))
      (node (ref "IC2") (pin "15") (pinfunction "VDDTX_15") (pintype "power_in"))
      (node (ref "IC2") (pin "19") (pinfunction "VDDRX_19") (pintype "power_in"))
      (node (ref "IC2") (pin "20") (pinfunction "VDDPLL_20") (pintype "power_in"))
      (node (ref "IC2") (pin "25") (pinfunction "VDDOSC_25") (pintype "power_in"))
      (node (ref "IC2") (pin "28") (pinfunction "VDD_28") (pintype "power_in"))
      (node (ref "L1") (pin "1") (pinfunction "1_1") (pintype "passive"))
      (node (ref "L2") (pin "1") (pinfunction "1_1") (pintype "passive"))
    )
    (net (code "54") (name "Net-(IC3-OUT)") (class "Default")
      (node (ref "CE1") (pin "+") (pinfunction "+_+") (pintype "passive"))
      (node (ref "IC3") (pin "2") (pinfunction "OUT_2") (pintype "passive"))
      (node (ref "L2") (pin "2") (pinfunction "2_2") (pintype "passive"))
    )
    (net (code "55") (name "Net-(IC4A-I)") (class "Default")
      (node (ref "C19") (pin "1") (pinfunction "1_1") (pintype "passive"))
      (node (ref "IC4") (pin "1") (pinfunction "I_1") (pintype "input"))
      (node (ref "R12") (pin "2") (pinfunction "2_2") (pintype "passive"))
    )
    (net (code "56") (name "Net-(IC4A-O)") (class "Default")
      (node (ref "C17") (pin "2") (pinfunction "2_2") (pintype "passive"))
      (node (ref "GAIN") (pin "5") (pinfunction "5_5") (pintype "passive"))
      (node (ref "IC4") (pin "2") (pinfunction "O_2") (pintype "output"))
      (node (ref "R12") (pin "1") (pinfunction "1_1") (pintype "passive"))
    )
    (net (code "57") (name "Net-(IC4B-I)") (class "Default")
      (node (ref "C17") (pin "1") (pinfunction "1_1") (pintype "passive"))
      (node (ref "IC4") (pin "3") (pinfunction "I_3") (pintype "input"))
      (node (ref "R13") (pin "2") (pinfunction "2_2") (pintype "passive"))
    )
    (net (code "58") (name "Net-(IC4B-O)") (class "Default")
      (node (ref "C18") (pin "2") (pinfunction "2_2") (pintype "passive"))
      (node (ref "GAIN") (pin "3") (pinfunction "3_3") (pintype "passive"))
      (node (ref "IC4") (pin "4") (pinfunction "O_4") (pintype "output"))
      (node (ref "R13") (pin "1") (pinfunction "1_1") (pintype "passive"))
    )
    (net (code "59") (name "Net-(IC4C-I)") (class "Default")
      (node (ref "C18") (pin "1") (pinfunction "1_1") (pintype "passive"))
      (node (ref "IC4") (pin "5") (pinfunction "I_5") (pintype "input"))
      (node (ref "R14") (pin "2") (pinfunction "2_2") (pintype "passive"))
    )
    (net (code "60") (name "Net-(IC4C-O)") (class "Default")
      (node (ref "GAIN") (pin "1") (pinfunction "1_1") (pintype "passive"))
      (node (ref "IC4") (pin "6") (pinfunction "O_6") (pintype "output"))
      (node (ref "R14") (pin "1") (pinfunction "1_1") (pintype "passive"))
    )
    (net (code "61") (name "Net-(J4-PadL1A)") (class "Default")
      (node (ref "J4") (pin "L1A") (pinfunction "L1A_L1A") (pintype "bidirectional"))
      (node (ref "RB") (pin "1") (pinfunction "1_1") (pintype "passive"))
    )
    (net (code "62") (name "Net-(J4-PadL2A)") (class "Default")
      (node (ref "J4") (pin "L2A") (pinfunction "L2A_L2A") (pintype "bidirectional"))
      (node (ref "RA") (pin "1") (pinfunction "1_1") (pintype "passive"))
    )
    (net (code "63") (name "Net-(J4-TX0)") (class "Default")
      (node (ref "C11") (pin "2") (pinfunction "2_2") (pintype "passive"))
      (node (ref "J4") (pin "3") (pinfunction "TX0_3") (pintype "bidirectional"))
      (node (ref "L1") (pin "2") (pinfunction "2_2") (pintype "passive"))
      (node (ref "R2") (pin "2") (pinfunction "2_2") (pintype "passive"))
      (node (ref "R3") (pin "1") (pinfunction "1_1") (pintype "passive"))
    )
    (net (code "64") (name "Net-(J33-P$1)") (class "Default")
      (node (ref "J33") (pin "1") (pinfunction "P$1_1") (pintype "bidirectional"))
      (node (ref "R1") (pin "2") (pinfunction "2_2") (pintype "passive"))
    )
    (net (code "65") (name "VCC") (class "Default")
      (node (ref "CE2") (pin "+") (pinfunction "+_+") (pintype "passive"))
      (node (ref "D2") (pin "A") (pinfunction "A_A") (pintype "passive"))
      (node (ref "IC3") (pin "3") (pinfunction "IN_3") (pintype "input"))
      (node (ref "R10") (pin "2") (pinfunction "2_2") (pintype "passive"))
      (node (ref "X1") (pin "1") (pinfunction "1_1") (pintype "passive"))
    )
    (net (code "66") (name "unconnected-(IC2-CLKOUT-Pad3)") (class "Default")
      (node (ref "IC2") (pin "3") (pinfunction "CLKOUT_3") (pintype "output"))
    )
    (net (code "67") (name "unconnected-(IC2-INT-Pad4)") (class "Default")
      (node (ref "IC2") (pin "4") (pinfunction "INT_4") (pintype "output"))
    )
    (net (code "68") (name "unconnected-(IC2-WOL-Pad5)") (class "Default")
      (node (ref "IC2") (pin "5") (pinfunction "WOL_5") (pintype "output"))
    )
    (net (code "69") (name "unconnected-(IC4D-O-Pad8)") (class "Default")
      (node (ref "IC4") (pin "8") (pinfunction "O_8") (pintype "output"))
    )
    (net (code "70") (name "unconnected-(IC4E-O-Pad10)") (class "Default")
      (node (ref "IC4") (pin "10") (pinfunction "O_10") (pintype "output"))
    )
    (net (code "71") (name "unconnected-(IC4F-O-Pad12)") (class "Default")
      (node (ref "IC4") (pin "12") (pinfunction "O_12") (pintype "output"))
    )
    (net (code "72") (name "unconnected-(J4-RX0-Pad6)") (class "Default")
      (node (ref "J4") (pin "6") (pinfunction "RX0_6") (pintype "bidirectional"))
    )
    (net (code "73") (name "unconnected-(J4-SHLD-PadS1)") (class "Default")
      (node (ref "J4") (pin "S1") (pinfunction "SHLD_S1") (pintype "bidirectional"))
    )
    (net (code "74") (name "unconnected-(J4-SHLD-PadS2)") (class "Default")
      (node (ref "J4") (pin "S2") (pinfunction "SHLD_S2") (pintype "bidirectional"))
    )
  )
)
